# SZG-PMODshield-TXR.net
KiCad netlist of a schematic drawn in Altium Designer
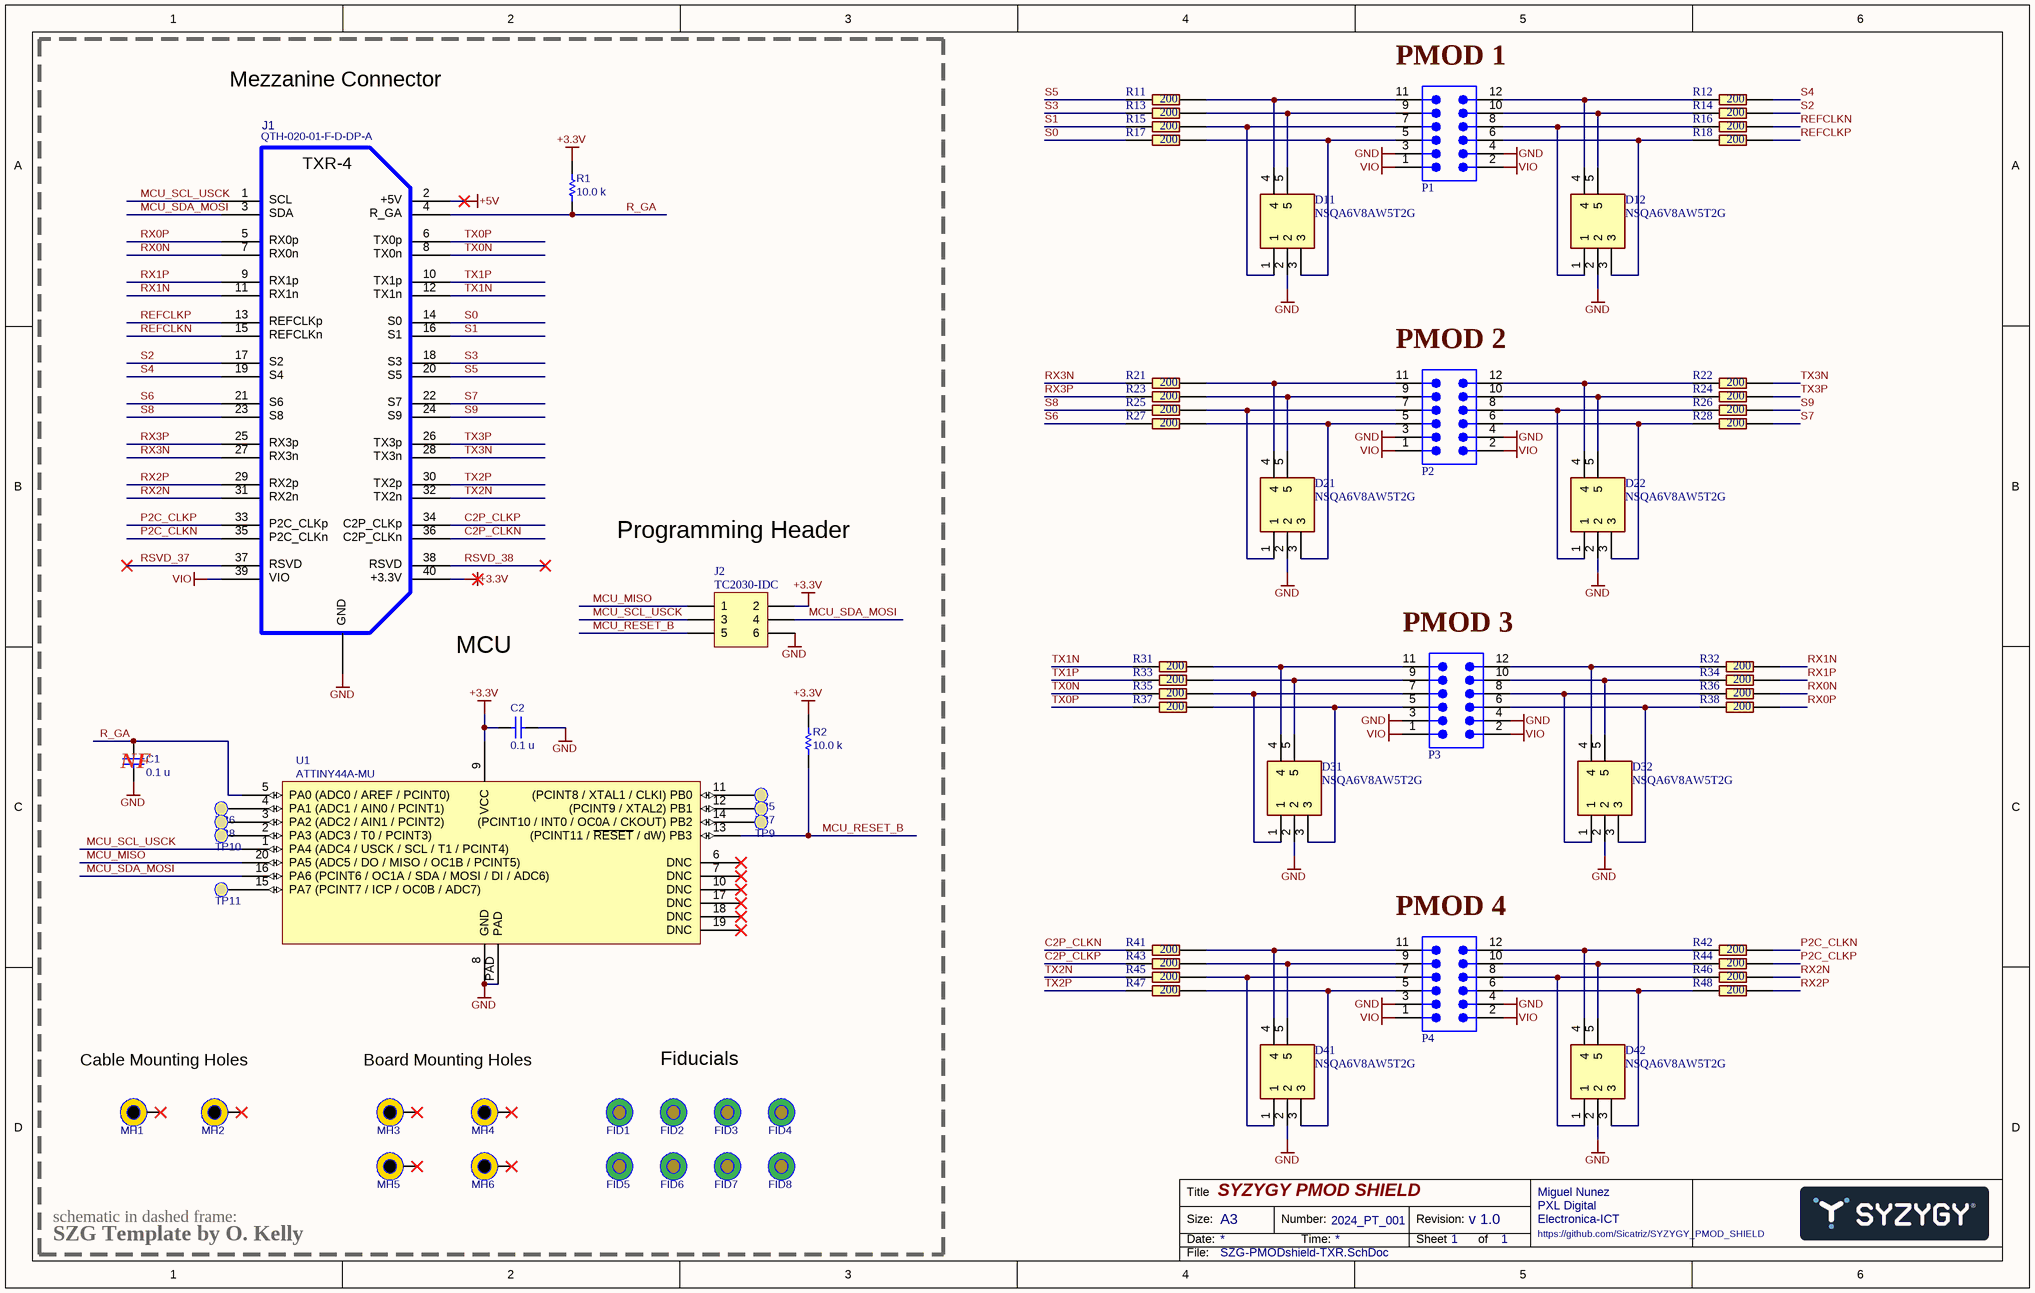
[diagram p0: SZG-PMODshield-TXR.SchDoc]

(export (version "E")
  (design (tool "Eeschema 10.0.6"))
  (components
    (comp (ref "C1")
      (value "0.1 u")
      (footprint "CAPC1005X06N")
      (description "Ceramic capacitor")
      (fields (field (name "MANUFACTURER") "Kemet") (field (name "PARTNUMBER") "000070"))
      (libsource (lib "Aligni") (part "Capacitor"))
    )
    (comp (ref "C2")
      (value "0.1 u")
      (footprint "CAPC1005X06N")
      (description "Ceramic capacitor")
      (fields (field (name "MANUFACTURER") "Kemet") (field (name "PARTNUMBER") "000070"))
      (libsource (lib "Aligni") (part "Capacitor"))
    )
    (comp (ref "D11")
      (value "NSQA6V8AW5T2G")
      (footprint "SZG-footprint-TXR:SOT65P210X110-5N")
      (description "Diode")
      (fields (field (name "MOUSER PART NUMBER") "863-NSQA6V8AW5T2G"))
      (libsource (lib "SZG-schematicLIB-TXR") (part "NSQA6V8AW5T2G"))
    )
    (comp (ref "D12")
      (value "NSQA6V8AW5T2G")
      (footprint "SZG-footprint-TXR:SOT65P210X110-5N")
      (description "Diode")
      (fields (field (name "MOUSER PART NUMBER") "863-NSQA6V8AW5T2G"))
      (libsource (lib "SZG-schematicLIB-TXR") (part "NSQA6V8AW5T2G"))
    )
    (comp (ref "D21")
      (value "NSQA6V8AW5T2G")
      (footprint "SZG-footprint-TXR:SOT65P210X110-5N")
      (description "Diode")
      (fields (field (name "MOUSER PART NUMBER") "863-NSQA6V8AW5T2G"))
      (libsource (lib "SZG-schematicLIB-TXR") (part "NSQA6V8AW5T2G"))
    )
    (comp (ref "D22")
      (value "NSQA6V8AW5T2G")
      (footprint "SZG-footprint-TXR:SOT65P210X110-5N")
      (description "Diode")
      (fields (field (name "MOUSER PART NUMBER") "863-NSQA6V8AW5T2G"))
      (libsource (lib "SZG-schematicLIB-TXR") (part "NSQA6V8AW5T2G"))
    )
    (comp (ref "D31")
      (value "NSQA6V8AW5T2G")
      (footprint "SZG-footprint-TXR:SOT65P210X110-5N")
      (description "Diode")
      (fields (field (name "MOUSER PART NUMBER") "863-NSQA6V8AW5T2G"))
      (libsource (lib "SZG-schematicLIB-TXR") (part "NSQA6V8AW5T2G"))
    )
    (comp (ref "D32")
      (value "NSQA6V8AW5T2G")
      (footprint "SZG-footprint-TXR:SOT65P210X110-5N")
      (description "Diode")
      (fields (field (name "MOUSER PART NUMBER") "863-NSQA6V8AW5T2G"))
      (libsource (lib "SZG-schematicLIB-TXR") (part "NSQA6V8AW5T2G"))
    )
    (comp (ref "D41")
      (value "NSQA6V8AW5T2G")
      (footprint "SZG-footprint-TXR:SOT65P210X110-5N")
      (description "Diode")
      (fields (field (name "MOUSER PART NUMBER") "863-NSQA6V8AW5T2G"))
      (libsource (lib "SZG-schematicLIB-TXR") (part "NSQA6V8AW5T2G"))
    )
    (comp (ref "D42")
      (value "NSQA6V8AW5T2G")
      (footprint "SZG-footprint-TXR:SOT65P210X110-5N")
      (description "Diode")
      (fields (field (name "MOUSER PART NUMBER") "863-NSQA6V8AW5T2G"))
      (libsource (lib "SZG-schematicLIB-TXR") (part "NSQA6V8AW5T2G"))
    )
    (comp (ref "FID1")
      (value "FIDUCIAL")
      (footprint "FID1MM/2MM-SS")
      (description "PCB fiducial")
      (libsource (lib "SZG-schematicLIB-TXR") (part "FIDUCIAL"))
    )
    (comp (ref "FID2")
      (value "FIDUCIAL")
      (footprint "FID1MM/2MM-SS")
      (description "PCB fiducial")
      (libsource (lib "SZG-schematicLIB-TXR") (part "FIDUCIAL"))
    )
    (comp (ref "FID3")
      (value "FIDUCIAL")
      (footprint "FID1MM/2MM-SS")
      (description "PCB fiducial")
      (libsource (lib "SZG-schematicLIB-TXR") (part "FIDUCIAL"))
    )
    (comp (ref "FID4")
      (value "FIDUCIAL")
      (footprint "FID1MM/2MM-SS")
      (description "PCB fiducial")
      (libsource (lib "SZG-schematicLIB-TXR") (part "FIDUCIAL"))
    )
    (comp (ref "FID5")
      (value "FIDUCIAL")
      (footprint "FID1MM/2MM-SS")
      (description "PCB fiducial")
      (libsource (lib "SZG-schematicLIB-TXR") (part "FIDUCIAL"))
    )
    (comp (ref "FID6")
      (value "FIDUCIAL")
      (footprint "FID1MM/2MM-SS")
      (description "PCB fiducial")
      (libsource (lib "SZG-schematicLIB-TXR") (part "FIDUCIAL"))
    )
    (comp (ref "FID7")
      (value "FIDUCIAL")
      (footprint "FID1MM/2MM-SS")
      (description "PCB fiducial")
      (libsource (lib "SZG-schematicLIB-TXR") (part "FIDUCIAL"))
    )
    (comp (ref "FID8")
      (value "FIDUCIAL")
      (footprint "FID1MM/2MM-SS")
      (description "PCB fiducial")
      (libsource (lib "SZG-schematicLIB-TXR") (part "FIDUCIAL"))
    )
    (comp (ref "J1")
      (value "40-pin, ground protection in middle")
      (footprint "QTH-020-01-X-D-DP-A-L")
      (description "0.5mm hi-speed, high-density header (female)")
      (fields
        (field (name "MANUFACTURER") "Samtec")
        (field (name "MANUFACTURER_PN") "QTH-020-01-F-D-DP-A")
        (field (name "ALIGNIPARTNUMBER") "001605")
      )
      (libsource (lib "Aligni") (part "QTH-DP_QSH-DP-020"))
    )
    (comp (ref "J2")
      (value "~")
      (footprint "TC2030-DUAL")
      (description "Tag-Connect 6-pin Plug-of-Nails spring-pin cable footprint")
      (fields
        (field (name "ALIGNIPARTNUMBER") "002062")
        (field (name "MANUFACTURER") "Tag-Connect")
        (field (name "MANUFACTURER_PN") "TC2030-IDC")
      )
      (libsource (lib "Aligni") (part "Header 3X2"))
    )
    (comp (ref "MH1")
      (value "MTG")
      (footprint "MTG-3.2/6.5-PTH")
      (description "Mounting hole")
      (libsource (lib "SZG-schematicLIB-TXR") (part "MTG"))
    )
    (comp (ref "MH2")
      (value "MTG")
      (footprint "MTG-3.2/6.5-PTH")
      (description "Mounting hole")
      (libsource (lib "SZG-schematicLIB-TXR") (part "MTG"))
    )
    (comp (ref "MH3")
      (value "MTG")
      (footprint "MTG-3.2/6.5-PTH")
      (description "Mounting hole")
      (libsource (lib "SZG-schematicLIB-TXR") (part "MTG"))
    )
    (comp (ref "MH4")
      (value "MTG")
      (footprint "MTG-3.2/6.5-PTH")
      (description "Mounting hole")
      (libsource (lib "SZG-schematicLIB-TXR") (part "MTG"))
    )
    (comp (ref "MH5")
      (value "MTG")
      (footprint "MTG-3.2/6.5-PTH")
      (description "Mounting hole")
      (libsource (lib "SZG-schematicLIB-TXR") (part "MTG"))
    )
    (comp (ref "MH6")
      (value "MTG")
      (footprint "MTG-3.2/6.5-PTH")
      (description "Mounting hole")
      (libsource (lib "SZG-schematicLIB-TXR") (part "MTG"))
    )
    (comp (ref "P1")
      (value "61301221021")
      (footprint "SZG-footprint-TXR:61301221021")
      (description "WR-PHD Pin Header, THT, Angled, pitch 2.54mm, 2 Row, 12P")
      (fields (field (name "MANUFACTURER") "Wurth Elektronik"))
      (libsource (lib "SZG-schematicLIB-TXR") (part "61301221021"))
    )
    (comp (ref "P2")
      (value "61301221021")
      (footprint "SZG-footprint-TXR:61301221021")
      (description "WR-PHD Pin Header, THT, Angled, pitch 2.54mm, 2 Row, 12P")
      (fields (field (name "MANUFACTURER") "Wurth Elektronik"))
      (libsource (lib "SZG-schematicLIB-TXR") (part "61301221021"))
    )
    (comp (ref "P3")
      (value "61301221121")
      (footprint "61301221121")
      (description "WR-PHD Pin Header, THT, Vertical, pitch 2.54mm, 2 Row, 12P")
      (fields (field (name "MANUFACTURER") "Wurth Elektronik"))
      (libsource (lib "SZG-schematicLIB-TXR") (part "61301221121"))
    )
    (comp (ref "P4")
      (value "61301221121")
      (footprint "61301221121")
      (description "WR-PHD Pin Header, THT, Vertical, pitch 2.54mm, 2 Row, 12P")
      (fields (field (name "MANUFACTURER") "Wurth Elektronik"))
      (libsource (lib "SZG-schematicLIB-TXR") (part "61301221121"))
    )
    (comp (ref "R1")
      (value "10.0 k")
      (footprint "RESC1005X06N")
      (description "Thick-film resistor")
      (fields (field (name "MANUFACTURER") "Vishay") (field (name "PARTNUMBER") "001521"))
      (libsource (lib "Aligni") (part "Resistor"))
    )
    (comp (ref "R2")
      (value "10.0 k")
      (footprint "RESC1005X06N")
      (description "Thick-film resistor")
      (fields (field (name "MANUFACTURER") "Vishay") (field (name "PARTNUMBER") "001521"))
      (libsource (lib "Aligni") (part "Resistor"))
    )
    (comp (ref "R11")
      (value "200")
      (footprint "SZG-footprint-TXR:RESC2012X50N")
      (description "Resistor")
      (fields (field (name "MANUFACTURER_PART_NUMBER") "CRCW08055K60JNEA"))
      (libsource (lib "SZG-schematicLIB-TXR") (part "0805_SMD_Resistor"))
    )
    (comp (ref "R12")
      (value "200")
      (footprint "SZG-footprint-TXR:RESC2012X50N")
      (description "Resistor")
      (fields (field (name "MANUFACTURER_PART_NUMBER") "CRCW08055K60JNEA"))
      (libsource (lib "SZG-schematicLIB-TXR") (part "0805_SMD_Resistor"))
    )
    (comp (ref "R13")
      (value "200")
      (footprint "SZG-footprint-TXR:RESC2012X50N")
      (description "Resistor")
      (fields (field (name "MANUFACTURER_PART_NUMBER") "CRCW08055K60JNEA"))
      (libsource (lib "SZG-schematicLIB-TXR") (part "0805_SMD_Resistor"))
    )
    (comp (ref "R14")
      (value "200")
      (footprint "SZG-footprint-TXR:RESC2012X50N")
      (description "Resistor")
      (fields (field (name "MANUFACTURER_PART_NUMBER") "CRCW08055K60JNEA"))
      (libsource (lib "SZG-schematicLIB-TXR") (part "0805_SMD_Resistor"))
    )
    (comp (ref "R15")
      (value "200")
      (footprint "SZG-footprint-TXR:RESC2012X50N")
      (description "Resistor")
      (fields (field (name "MANUFACTURER_PART_NUMBER") "CRCW08055K60JNEA"))
      (libsource (lib "SZG-schematicLIB-TXR") (part "0805_SMD_Resistor"))
    )
    (comp (ref "R16")
      (value "200")
      (footprint "SZG-footprint-TXR:RESC2012X50N")
      (description "Resistor")
      (fields (field (name "MANUFACTURER_PART_NUMBER") "CRCW08055K60JNEA"))
      (libsource (lib "SZG-schematicLIB-TXR") (part "0805_SMD_Resistor"))
    )
    (comp (ref "R17")
      (value "200")
      (footprint "SZG-footprint-TXR:RESC2012X50N")
      (description "Resistor")
      (fields (field (name "MANUFACTURER_PART_NUMBER") "CRCW08055K60JNEA"))
      (libsource (lib "SZG-schematicLIB-TXR") (part "0805_SMD_Resistor"))
    )
    (comp (ref "R18")
      (value "200")
      (footprint "SZG-footprint-TXR:RESC2012X50N")
      (description "Resistor")
      (fields (field (name "MANUFACTURER_PART_NUMBER") "CRCW08055K60JNEA"))
      (libsource (lib "SZG-schematicLIB-TXR") (part "0805_SMD_Resistor"))
    )
    (comp (ref "R21")
      (value "200")
      (footprint "SZG-footprint-TXR:RESC2012X50N")
      (description "Resistor")
      (fields (field (name "MANUFACTURER_PART_NUMBER") "CRCW08055K60JNEA"))
      (libsource (lib "SZG-schematicLIB-TXR") (part "0805_SMD_Resistor"))
    )
    (comp (ref "R22")
      (value "200")
      (footprint "SZG-footprint-TXR:RESC2012X50N")
      (description "Resistor")
      (fields (field (name "MANUFACTURER_PART_NUMBER") "CRCW08055K60JNEA"))
      (libsource (lib "SZG-schematicLIB-TXR") (part "0805_SMD_Resistor"))
    )
    (comp (ref "R23")
      (value "200")
      (footprint "SZG-footprint-TXR:RESC2012X50N")
      (description "Resistor")
      (fields (field (name "MANUFACTURER_PART_NUMBER") "CRCW08055K60JNEA"))
      (libsource (lib "SZG-schematicLIB-TXR") (part "0805_SMD_Resistor"))
    )
    (comp (ref "R24")
      (value "200")
      (footprint "SZG-footprint-TXR:RESC2012X50N")
      (description "Resistor")
      (fields (field (name "MANUFACTURER_PART_NUMBER") "CRCW08055K60JNEA"))
      (libsource (lib "SZG-schematicLIB-TXR") (part "0805_SMD_Resistor"))
    )
    (comp (ref "R25")
      (value "200")
      (footprint "SZG-footprint-TXR:RESC2012X50N")
      (description "Resistor")
      (fields (field (name "MANUFACTURER_PART_NUMBER") "CRCW08055K60JNEA"))
      (libsource (lib "SZG-schematicLIB-TXR") (part "0805_SMD_Resistor"))
    )
    (comp (ref "R26")
      (value "200")
      (footprint "SZG-footprint-TXR:RESC2012X50N")
      (description "Resistor")
      (fields (field (name "MANUFACTURER_PART_NUMBER") "CRCW08055K60JNEA"))
      (libsource (lib "SZG-schematicLIB-TXR") (part "0805_SMD_Resistor"))
    )
    (comp (ref "R27")
      (value "200")
      (footprint "SZG-footprint-TXR:RESC2012X50N")
      (description "Resistor")
      (fields (field (name "MANUFACTURER_PART_NUMBER") "CRCW08055K60JNEA"))
      (libsource (lib "SZG-schematicLIB-TXR") (part "0805_SMD_Resistor"))
    )
    (comp (ref "R28")
      (value "200")
      (footprint "SZG-footprint-TXR:RESC2012X50N")
      (description "Resistor")
      (fields (field (name "MANUFACTURER_PART_NUMBER") "CRCW08055K60JNEA"))
      (libsource (lib "SZG-schematicLIB-TXR") (part "0805_SMD_Resistor"))
    )
    (comp (ref "R31")
      (value "200")
      (footprint "SZG-footprint-TXR:RESC2012X50N")
      (description "Resistor")
      (fields (field (name "MANUFACTURER_PART_NUMBER") "CRCW08055K60JNEA"))
      (libsource (lib "SZG-schematicLIB-TXR") (part "0805_SMD_Resistor"))
    )
    (comp (ref "R32")
      (value "200")
      (footprint "SZG-footprint-TXR:RESC2012X50N")
      (description "Resistor")
      (fields (field (name "MANUFACTURER_PART_NUMBER") "CRCW08055K60JNEA"))
      (libsource (lib "SZG-schematicLIB-TXR") (part "0805_SMD_Resistor"))
    )
    (comp (ref "R33")
      (value "200")
      (footprint "SZG-footprint-TXR:RESC2012X50N")
      (description "Resistor")
      (fields (field (name "MANUFACTURER_PART_NUMBER") "CRCW08055K60JNEA"))
      (libsource (lib "SZG-schematicLIB-TXR") (part "0805_SMD_Resistor"))
    )
    (comp (ref "R34")
      (value "200")
      (footprint "SZG-footprint-TXR:RESC2012X50N")
      (description "Resistor")
      (fields (field (name "MANUFACTURER_PART_NUMBER") "CRCW08055K60JNEA"))
      (libsource (lib "SZG-schematicLIB-TXR") (part "0805_SMD_Resistor"))
    )
    (comp (ref "R35")
      (value "200")
      (footprint "SZG-footprint-TXR:RESC2012X50N")
      (description "Resistor")
      (fields (field (name "MANUFACTURER_PART_NUMBER") "CRCW08055K60JNEA"))
      (libsource (lib "SZG-schematicLIB-TXR") (part "0805_SMD_Resistor"))
    )
    (comp (ref "R36")
      (value "200")
      (footprint "SZG-footprint-TXR:RESC2012X50N")
      (description "Resistor")
      (fields (field (name "MANUFACTURER_PART_NUMBER") "CRCW08055K60JNEA"))
      (libsource (lib "SZG-schematicLIB-TXR") (part "0805_SMD_Resistor"))
    )
    (comp (ref "R37")
      (value "200")
      (footprint "SZG-footprint-TXR:RESC2012X50N")
      (description "Resistor")
      (fields (field (name "MANUFACTURER_PART_NUMBER") "CRCW08055K60JNEA"))
      (libsource (lib "SZG-schematicLIB-TXR") (part "0805_SMD_Resistor"))
    )
    (comp (ref "R38")
      (value "200")
      (footprint "SZG-footprint-TXR:RESC2012X50N")
      (description "Resistor")
      (fields (field (name "MANUFACTURER_PART_NUMBER") "CRCW08055K60JNEA"))
      (libsource (lib "SZG-schematicLIB-TXR") (part "0805_SMD_Resistor"))
    )
    (comp (ref "R41")
      (value "200")
      (footprint "SZG-footprint-TXR:RESC2012X50N")
      (description "Resistor")
      (fields (field (name "MANUFACTURER_PART_NUMBER") "CRCW08055K60JNEA"))
      (libsource (lib "SZG-schematicLIB-TXR") (part "0805_SMD_Resistor"))
    )
    (comp (ref "R42")
      (value "200")
      (footprint "SZG-footprint-TXR:RESC2012X50N")
      (description "Resistor")
      (fields (field (name "MANUFACTURER_PART_NUMBER") "CRCW08055K60JNEA"))
      (libsource (lib "SZG-schematicLIB-TXR") (part "0805_SMD_Resistor"))
    )
    (comp (ref "R43")
      (value "200")
      (footprint "SZG-footprint-TXR:RESC2012X50N")
      (description "Resistor")
      (fields (field (name "MANUFACTURER_PART_NUMBER") "CRCW08055K60JNEA"))
      (libsource (lib "SZG-schematicLIB-TXR") (part "0805_SMD_Resistor"))
    )
    (comp (ref "R44")
      (value "200")
      (footprint "SZG-footprint-TXR:RESC2012X50N")
      (description "Resistor")
      (fields (field (name "MANUFACTURER_PART_NUMBER") "CRCW08055K60JNEA"))
      (libsource (lib "SZG-schematicLIB-TXR") (part "0805_SMD_Resistor"))
    )
    (comp (ref "R45")
      (value "200")
      (footprint "SZG-footprint-TXR:RESC2012X50N")
      (description "Resistor")
      (fields (field (name "MANUFACTURER_PART_NUMBER") "CRCW08055K60JNEA"))
      (libsource (lib "SZG-schematicLIB-TXR") (part "0805_SMD_Resistor"))
    )
    (comp (ref "R46")
      (value "200")
      (footprint "SZG-footprint-TXR:RESC2012X50N")
      (description "Resistor")
      (fields (field (name "MANUFACTURER_PART_NUMBER") "CRCW08055K60JNEA"))
      (libsource (lib "SZG-schematicLIB-TXR") (part "0805_SMD_Resistor"))
    )
    (comp (ref "R47")
      (value "200")
      (footprint "SZG-footprint-TXR:RESC2012X50N")
      (description "Resistor")
      (fields (field (name "MANUFACTURER_PART_NUMBER") "CRCW08055K60JNEA"))
      (libsource (lib "SZG-schematicLIB-TXR") (part "0805_SMD_Resistor"))
    )
    (comp (ref "R48")
      (value "200")
      (footprint "SZG-footprint-TXR:RESC2012X50N")
      (description "Resistor")
      (fields (field (name "MANUFACTURER_PART_NUMBER") "CRCW08055K60JNEA"))
      (libsource (lib "SZG-schematicLIB-TXR") (part "0805_SMD_Resistor"))
    )
    (comp (ref "TP5")
      (value "TESTPOINT-SMD20")
      (footprint "TP-SMD20")
      (description "Test point, surface-mount, 20mil")
      (libsource (lib "SZG-schematicLIB-TXR") (part "TESTPOINT-SMD20"))
    )
    (comp (ref "TP6")
      (value "TESTPOINT-SMD20")
      (footprint "TP-SMD20")
      (description "Test point, surface-mount, 20mil")
      (libsource (lib "SZG-schematicLIB-TXR") (part "TESTPOINT-SMD20"))
    )
    (comp (ref "TP7")
      (value "TESTPOINT-SMD20")
      (footprint "TP-SMD20")
      (description "Test point, surface-mount, 20mil")
      (libsource (lib "SZG-schematicLIB-TXR") (part "TESTPOINT-SMD20"))
    )
    (comp (ref "TP8")
      (value "TESTPOINT-SMD20")
      (footprint "TP-SMD20")
      (description "Test point, surface-mount, 20mil")
      (libsource (lib "SZG-schematicLIB-TXR") (part "TESTPOINT-SMD20"))
    )
    (comp (ref "TP9")
      (value "TESTPOINT-SMD20")
      (footprint "TP-SMD20")
      (description "Test point, surface-mount, 20mil")
      (libsource (lib "SZG-schematicLIB-TXR") (part "TESTPOINT-SMD20"))
    )
    (comp (ref "TP10")
      (value "TESTPOINT-SMD20")
      (footprint "TP-SMD20")
      (description "Test point, surface-mount, 20mil")
      (libsource (lib "SZG-schematicLIB-TXR") (part "TESTPOINT-SMD20"))
    )
    (comp (ref "TP11")
      (value "TESTPOINT-SMD20")
      (footprint "TP-SMD20")
      (description "Test point, surface-mount, 20mil")
      (libsource (lib "SZG-schematicLIB-TXR") (part "TESTPOINT-SMD20"))
    )
    (comp (ref "U1")
      (value "ATTINY44A-MU")
      (footprint "QFN-EP-20")
      (description "8-bit MCU, 4 KB flash, 256 bytes EEPROM")
      (fields (field (name "MANUFACTURER") "Microchip") (field (name "PARTNUMBER") "001552"))
      (libsource (lib "Aligni") (part "ATTINYx4A-MU"))
    )
  )
  (nets
    (net (code "1") (name "+3.3V") (class "Default")
      (node (ref "C2") (pin "2") (pinfunction "2_2") (pintype "passive"))
      (node (ref "J1") (pin "40") (pinfunction "40_40") (pintype "passive"))
      (node (ref "J2") (pin "2") (pinfunction "2_2") (pintype "passive"))
      (node (ref "R1") (pin "2") (pinfunction "2_2") (pintype "passive"))
      (node (ref "R2") (pin "2") (pinfunction "2_2") (pintype "passive"))
      (node (ref "U1") (pin "9") (pinfunction "VCC_9") (pintype "power_in"))
    )
    (net (code "2") (name "+5V") (class "Default")
      (node (ref "J1") (pin "2") (pinfunction "2_2") (pintype "passive"))
    )
    (net (code "3") (name "/C2P_CLKN") (class "Default")
      (node (ref "J1") (pin "36") (pinfunction "36_36") (pintype "passive"))
      (node (ref "R41") (pin "1") (pinfunction "1_1") (pintype "passive"))
    )
    (net (code "4") (name "/C2P_CLKP") (class "Default")
      (node (ref "J1") (pin "34") (pinfunction "34_34") (pintype "passive"))
      (node (ref "R43") (pin "1") (pinfunction "1_1") (pintype "passive"))
    )
    (net (code "5") (name "/MCU_MISO") (class "Default")
      (node (ref "J2") (pin "1") (pinfunction "1_1") (pintype "passive"))
      (node (ref "U1") (pin "20") (pinfunction "PA5_(ADC5_/_DO_/_MISO_/_OC1B_/_PCINT5)_20") (pintype "bidirectional"))
    )
    (net (code "6") (name "/MCU_RESET_B") (class "Default")
      (node (ref "J2") (pin "5") (pinfunction "5_5") (pintype "passive"))
      (node (ref "R2") (pin "1") (pinfunction "1_1") (pintype "passive"))
      (node (ref "U1") (pin "13") (pinfunction "(PCINT11_/_~{RESET}_/_dW)_PB3_13") (pintype "bidirectional"))
    )
    (net (code "7") (name "/MCU_SCL_USCK") (class "Default")
      (node (ref "J1") (pin "1") (pinfunction "1_1") (pintype "passive"))
      (node (ref "J2") (pin "3") (pinfunction "3_3") (pintype "passive"))
      (node (ref "U1") (pin "1") (pinfunction "PA4_(ADC4_/_USCK_/_SCL_/_T1_/_PCINT4)_1") (pintype "bidirectional"))
    )
    (net (code "8") (name "/MCU_SDA_MOSI") (class "Default")
      (node (ref "J1") (pin "3") (pinfunction "3_3") (pintype "passive"))
      (node (ref "J2") (pin "4") (pinfunction "4_4") (pintype "passive"))
      (node (ref "U1") (pin "16") (pinfunction "PA6_(PCINT6_/_OC1A_/_SDA_/_MOSI_/_DI_/_ADC6)_16") (pintype "bidirectional"))
    )
    (net (code "9") (name "/P2C_CLKN") (class "Default")
      (node (ref "J1") (pin "35") (pinfunction "35_35") (pintype "passive"))
      (node (ref "R42") (pin "2") (pinfunction "2_2") (pintype "passive"))
    )
    (net (code "10") (name "/P2C_CLKP") (class "Default")
      (node (ref "J1") (pin "33") (pinfunction "33_33") (pintype "passive"))
      (node (ref "R44") (pin "2") (pinfunction "2_2") (pintype "passive"))
    )
    (net (code "11") (name "/REFCLKN") (class "Default")
      (node (ref "J1") (pin "15") (pinfunction "15_15") (pintype "passive"))
      (node (ref "R16") (pin "2") (pinfunction "2_2") (pintype "passive"))
    )
    (net (code "12") (name "/REFCLKP") (class "Default")
      (node (ref "J1") (pin "13") (pinfunction "13_13") (pintype "passive"))
      (node (ref "R18") (pin "2") (pinfunction "2_2") (pintype "passive"))
    )
    (net (code "13") (name "/RSVD_37") (class "Default")
      (node (ref "J1") (pin "37") (pinfunction "37_37") (pintype "passive+no_connect"))
    )
    (net (code "14") (name "/RSVD_38") (class "Default")
      (node (ref "J1") (pin "38") (pinfunction "38_38") (pintype "passive+no_connect"))
    )
    (net (code "15") (name "/RX0N") (class "Default")
      (node (ref "J1") (pin "7") (pinfunction "7_7") (pintype "passive"))
      (node (ref "R36") (pin "2") (pinfunction "2_2") (pintype "passive"))
    )
    (net (code "16") (name "/RX0P") (class "Default")
      (node (ref "J1") (pin "5") (pinfunction "5_5") (pintype "passive"))
      (node (ref "R38") (pin "2") (pinfunction "2_2") (pintype "passive"))
    )
    (net (code "17") (name "/RX1N") (class "Default")
      (node (ref "J1") (pin "11") (pinfunction "11_11") (pintype "passive"))
      (node (ref "R32") (pin "2") (pinfunction "2_2") (pintype "passive"))
    )
    (net (code "18") (name "/RX1P") (class "Default")
      (node (ref "J1") (pin "9") (pinfunction "9_9") (pintype "passive"))
      (node (ref "R34") (pin "2") (pinfunction "2_2") (pintype "passive"))
    )
    (net (code "19") (name "/RX2N") (class "Default")
      (node (ref "J1") (pin "31") (pinfunction "31_31") (pintype "passive"))
      (node (ref "R46") (pin "2") (pinfunction "2_2") (pintype "passive"))
    )
    (net (code "20") (name "/RX2P") (class "Default")
      (node (ref "J1") (pin "29") (pinfunction "29_29") (pintype "passive"))
      (node (ref "R48") (pin "2") (pinfunction "2_2") (pintype "passive"))
    )
    (net (code "21") (name "/RX3N") (class "Default")
      (node (ref "J1") (pin "27") (pinfunction "27_27") (pintype "passive"))
      (node (ref "R21") (pin "1") (pinfunction "1_1") (pintype "passive"))
    )
    (net (code "22") (name "/RX3P") (class "Default")
      (node (ref "J1") (pin "25") (pinfunction "25_25") (pintype "passive"))
      (node (ref "R23") (pin "1") (pinfunction "1_1") (pintype "passive"))
    )
    (net (code "23") (name "/R_GA") (class "Default")
      (node (ref "C1") (pin "2") (pinfunction "2_2") (pintype "passive"))
      (node (ref "J1") (pin "4") (pinfunction "4_4") (pintype "passive"))
      (node (ref "R1") (pin "1") (pinfunction "1_1") (pintype "passive"))
      (node (ref "U1") (pin "5") (pinfunction "PA0_(ADC0_/_AREF_/_PCINT0)_5") (pintype "bidirectional"))
    )
    (net (code "24") (name "/S0") (class "Default")
      (node (ref "J1") (pin "14") (pinfunction "14_14") (pintype "passive"))
      (node (ref "R17") (pin "1") (pinfunction "1_1") (pintype "passive"))
    )
    (net (code "25") (name "/S1") (class "Default")
      (node (ref "J1") (pin "16") (pinfunction "16_16") (pintype "passive"))
      (node (ref "R15") (pin "1") (pinfunction "1_1") (pintype "passive"))
    )
    (net (code "26") (name "/S2") (class "Default")
      (node (ref "J1") (pin "17") (pinfunction "17_17") (pintype "passive"))
      (node (ref "R14") (pin "2") (pinfunction "2_2") (pintype "passive"))
    )
    (net (code "27") (name "/S3") (class "Default")
      (node (ref "J1") (pin "18") (pinfunction "18_18") (pintype "passive"))
      (node (ref "R13") (pin "1") (pinfunction "1_1") (pintype "passive"))
    )
    (net (code "28") (name "/S4") (class "Default")
      (node (ref "J1") (pin "19") (pinfunction "19_19") (pintype "passive"))
      (node (ref "R12") (pin "2") (pinfunction "2_2") (pintype "passive"))
    )
    (net (code "29") (name "/S5") (class "Default")
      (node (ref "J1") (pin "20") (pinfunction "20_20") (pintype "passive"))
      (node (ref "R11") (pin "1") (pinfunction "1_1") (pintype "passive"))
    )
    (net (code "30") (name "/S6") (class "Default")
      (node (ref "J1") (pin "21") (pinfunction "21_21") (pintype "passive"))
      (node (ref "R27") (pin "1") (pinfunction "1_1") (pintype "passive"))
    )
    (net (code "31") (name "/S7") (class "Default")
      (node (ref "J1") (pin "22") (pinfunction "22_22") (pintype "passive"))
      (node (ref "R28") (pin "2") (pinfunction "2_2") (pintype "passive"))
    )
    (net (code "32") (name "/S8") (class "Default")
      (node (ref "J1") (pin "23") (pinfunction "23_23") (pintype "passive"))
      (node (ref "R25") (pin "1") (pinfunction "1_1") (pintype "passive"))
    )
    (net (code "33") (name "/S9") (class "Default")
      (node (ref "J1") (pin "24") (pinfunction "24_24") (pintype "passive"))
      (node (ref "R26") (pin "2") (pinfunction "2_2") (pintype "passive"))
    )
    (net (code "34") (name "/TX0N") (class "Default")
      (node (ref "J1") (pin "8") (pinfunction "8_8") (pintype "passive"))
      (node (ref "R35") (pin "1") (pinfunction "1_1") (pintype "passive"))
    )
    (net (code "35") (name "/TX0P") (class "Default")
      (node (ref "J1") (pin "6") (pinfunction "6_6") (pintype "passive"))
      (node (ref "R37") (pin "1") (pinfunction "1_1") (pintype "passive"))
    )
    (net (code "36") (name "/TX1N") (class "Default")
      (node (ref "J1") (pin "12") (pinfunction "12_12") (pintype "passive"))
      (node (ref "R31") (pin "1") (pinfunction "1_1") (pintype "passive"))
    )
    (net (code "37") (name "/TX1P") (class "Default")
      (node (ref "J1") (pin "10") (pinfunction "10_10") (pintype "passive"))
      (node (ref "R33") (pin "1") (pinfunction "1_1") (pintype "passive"))
    )
    (net (code "38") (name "/TX2N") (class "Default")
      (node (ref "J1") (pin "32") (pinfunction "32_32") (pintype "passive"))
      (node (ref "R45") (pin "1") (pinfunction "1_1") (pintype "passive"))
    )
    (net (code "39") (name "/TX2P") (class "Default")
      (node (ref "J1") (pin "30") (pinfunction "30_30") (pintype "passive"))
      (node (ref "R47") (pin "1") (pinfunction "1_1") (pintype "passive"))
    )
    (net (code "40") (name "/TX3N") (class "Default")
      (node (ref "J1") (pin "28") (pinfunction "28_28") (pintype "passive"))
      (node (ref "R22") (pin "2") (pinfunction "2_2") (pintype "passive"))
    )
    (net (code "41") (name "/TX3P") (class "Default")
      (node (ref "J1") (pin "26") (pinfunction "26_26") (pintype "passive"))
      (node (ref "R24") (pin "2") (pinfunction "2_2") (pintype "passive"))
    )
    (net (code "42") (name "GND") (class "Default")
      (node (ref "C1") (pin "1") (pinfunction "1_1") (pintype "passive"))
      (node (ref "C2") (pin "1") (pinfunction "1_1") (pintype "passive"))
      (node (ref "D11") (pin "2") (pinfunction "2_2") (pintype "passive"))
      (node (ref "D12") (pin "2") (pinfunction "2_2") (pintype "passive"))
      (node (ref "D21") (pin "2") (pinfunction "2_2") (pintype "passive"))
      (node (ref "D22") (pin "2") (pinfunction "2_2") (pintype "passive"))
      (node (ref "D31") (pin "2") (pinfunction "2_2") (pintype "passive"))
      (node (ref "D32") (pin "2") (pinfunction "2_2") (pintype "passive"))
      (node (ref "D41") (pin "2") (pinfunction "2_2") (pintype "passive"))
      (node (ref "D42") (pin "2") (pinfunction "2_2") (pintype "passive"))
      (node (ref "J1") (pin "0") (pinfunction "GND_0") (pintype "passive"))
      (node (ref "J2") (pin "6") (pinfunction "6_6") (pintype "passive"))
      (node (ref "P1") (pin "3") (pinfunction "3_3") (pintype "passive"))
      (node (ref "P1") (pin "4") (pinfunction "4_4") (pintype "passive"))
      (node (ref "P2") (pin "3") (pinfunction "3_3") (pintype "passive"))
      (node (ref "P2") (pin "4") (pinfunction "4_4") (pintype "passive"))
      (node (ref "P3") (pin "3") (pinfunction "3_3") (pintype "passive"))
      (node (ref "P3") (pin "4") (pinfunction "4_4") (pintype "passive"))
      (node (ref "P4") (pin "3") (pinfunction "3_3") (pintype "passive"))
      (node (ref "P4") (pin "4") (pinfunction "4_4") (pintype "passive"))
      (node (ref "U1") (pin "8") (pinfunction "GND_8") (pintype "power_in"))
      (node (ref "U1") (pin "PAD") (pinfunction "PAD_PAD") (pintype "power_in"))
    )
    (net (code "43") (name "Net-(D11-Pad1)") (class "Default")
      (node (ref "D11") (pin "1") (pinfunction "1_1") (pintype "passive"))
      (node (ref "P1") (pin "7") (pinfunction "7_7") (pintype "passive"))
      (node (ref "R15") (pin "2") (pinfunction "2_2") (pintype "passive"))
    )
    (net (code "44") (name "Net-(D11-Pad3)") (class "Default")
      (node (ref "D11") (pin "3") (pinfunction "3_3") (pintype "passive"))
      (node (ref "P1") (pin "5") (pinfunction "5_5") (pintype "passive"))
      (node (ref "R17") (pin "2") (pinfunction "2_2") (pintype "passive"))
    )
    (net (code "45") (name "Net-(D11-Pad4)") (class "Default")
      (node (ref "D11") (pin "4") (pinfunction "4_4") (pintype "passive"))
      (node (ref "P1") (pin "11") (pinfunction "11_11") (pintype "passive"))
      (node (ref "R11") (pin "2") (pinfunction "2_2") (pintype "passive"))
    )
    (net (code "46") (name "Net-(D11-Pad5)") (class "Default")
      (node (ref "D11") (pin "5") (pinfunction "5_5") (pintype "passive"))
      (node (ref "P1") (pin "9") (pinfunction "9_9") (pintype "passive"))
      (node (ref "R13") (pin "2") (pinfunction "2_2") (pintype "passive"))
    )
    (net (code "47") (name "Net-(D12-Pad1)") (class "Default")
      (node (ref "D12") (pin "1") (pinfunction "1_1") (pintype "passive"))
      (node (ref "P1") (pin "8") (pinfunction "8_8") (pintype "passive"))
      (node (ref "R16") (pin "1") (pinfunction "1_1") (pintype "passive"))
    )
    (net (code "48") (name "Net-(D12-Pad3)") (class "Default")
      (node (ref "D12") (pin "3") (pinfunction "3_3") (pintype "passive"))
      (node (ref "P1") (pin "6") (pinfunction "6_6") (pintype "passive"))
      (node (ref "R18") (pin "1") (pinfunction "1_1") (pintype "passive"))
    )
    (net (code "49") (name "Net-(D12-Pad4)") (class "Default")
      (node (ref "D12") (pin "4") (pinfunction "4_4") (pintype "passive"))
      (node (ref "P1") (pin "12") (pinfunction "12_12") (pintype "passive"))
      (node (ref "R12") (pin "1") (pinfunction "1_1") (pintype "passive"))
    )
    (net (code "50") (name "Net-(D12-Pad5)") (class "Default")
      (node (ref "D12") (pin "5") (pinfunction "5_5") (pintype "passive"))
      (node (ref "P1") (pin "10") (pinfunction "10_10") (pintype "passive"))
      (node (ref "R14") (pin "1") (pinfunction "1_1") (pintype "passive"))
    )
    (net (code "51") (name "Net-(D21-Pad1)") (class "Default")
      (node (ref "D21") (pin "1") (pinfunction "1_1") (pintype "passive"))
      (node (ref "P2") (pin "7") (pinfunction "7_7") (pintype "passive"))
      (node (ref "R25") (pin "2") (pinfunction "2_2") (pintype "passive"))
    )
    (net (code "52") (name "Net-(D21-Pad3)") (class "Default")
      (node (ref "D21") (pin "3") (pinfunction "3_3") (pintype "passive"))
      (node (ref "P2") (pin "5") (pinfunction "5_5") (pintype "passive"))
      (node (ref "R27") (pin "2") (pinfunction "2_2") (pintype "passive"))
    )
    (net (code "53") (name "Net-(D21-Pad4)") (class "Default")
      (node (ref "D21") (pin "4") (pinfunction "4_4") (pintype "passive"))
      (node (ref "P2") (pin "11") (pinfunction "11_11") (pintype "passive"))
      (node (ref "R21") (pin "2") (pinfunction "2_2") (pintype "passive"))
    )
    (net (code "54") (name "Net-(D21-Pad5)") (class "Default")
      (node (ref "D21") (pin "5") (pinfunction "5_5") (pintype "passive"))
      (node (ref "P2") (pin "9") (pinfunction "9_9") (pintype "passive"))
      (node (ref "R23") (pin "2") (pinfunction "2_2") (pintype "passive"))
    )
    (net (code "55") (name "Net-(D22-Pad1)") (class "Default")
      (node (ref "D22") (pin "1") (pinfunction "1_1") (pintype "passive"))
      (node (ref "P2") (pin "8") (pinfunction "8_8") (pintype "passive"))
      (node (ref "R26") (pin "1") (pinfunction "1_1") (pintype "passive"))
    )
    (net (code "56") (name "Net-(D22-Pad3)") (class "Default")
      (node (ref "D22") (pin "3") (pinfunction "3_3") (pintype "passive"))
      (node (ref "P2") (pin "6") (pinfunction "6_6") (pintype "passive"))
      (node (ref "R28") (pin "1") (pinfunction "1_1") (pintype "passive"))
    )
    (net (code "57") (name "Net-(D22-Pad4)") (class "Default")
      (node (ref "D22") (pin "4") (pinfunction "4_4") (pintype "passive"))
      (node (ref "P2") (pin "12") (pinfunction "12_12") (pintype "passive"))
      (node (ref "R22") (pin "1") (pinfunction "1_1") (pintype "passive"))
    )
    (net (code "58") (name "Net-(D22-Pad5)") (class "Default")
      (node (ref "D22") (pin "5") (pinfunction "5_5") (pintype "passive"))
      (node (ref "P2") (pin "10") (pinfunction "10_10") (pintype "passive"))
      (node (ref "R24") (pin "1") (pinfunction "1_1") (pintype "passive"))
    )
    (net (code "59") (name "Net-(D31-Pad1)") (class "Default")
      (node (ref "D31") (pin "1") (pinfunction "1_1") (pintype "passive"))
      (node (ref "P3") (pin "7") (pinfunction "7_7") (pintype "passive"))
      (node (ref "R35") (pin "2") (pinfunction "2_2") (pintype "passive"))
    )
    (net (code "60") (name "Net-(D31-Pad3)") (class "Default")
      (node (ref "D31") (pin "3") (pinfunction "3_3") (pintype "passive"))
      (node (ref "P3") (pin "5") (pinfunction "5_5") (pintype "passive"))
      (node (ref "R37") (pin "2") (pinfunction "2_2") (pintype "passive"))
    )
    (net (code "61") (name "Net-(D31-Pad4)") (class "Default")
      (node (ref "D31") (pin "4") (pinfunction "4_4") (pintype "passive"))
      (node (ref "P3") (pin "11") (pinfunction "11_11") (pintype "passive"))
      (node (ref "R31") (pin "2") (pinfunction "2_2") (pintype "passive"))
    )
    (net (code "62") (name "Net-(D31-Pad5)") (class "Default")
      (node (ref "D31") (pin "5") (pinfunction "5_5") (pintype "passive"))
      (node (ref "P3") (pin "9") (pinfunction "9_9") (pintype "passive"))
      (node (ref "R33") (pin "2") (pinfunction "2_2") (pintype "passive"))
    )
    (net (code "63") (name "Net-(D32-Pad1)") (class "Default")
      (node (ref "D32") (pin "1") (pinfunction "1_1") (pintype "passive"))
      (node (ref "P3") (pin "8") (pinfunction "8_8") (pintype "passive"))
      (node (ref "R36") (pin "1") (pinfunction "1_1") (pintype "passive"))
    )
    (net (code "64") (name "Net-(D32-Pad3)") (class "Default")
      (node (ref "D32") (pin "3") (pinfunction "3_3") (pintype "passive"))
      (node (ref "P3") (pin "6") (pinfunction "6_6") (pintype "passive"))
      (node (ref "R38") (pin "1") (pinfunction "1_1") (pintype "passive"))
    )
    (net (code "65") (name "Net-(D32-Pad4)") (class "Default")
      (node (ref "D32") (pin "4") (pinfunction "4_4") (pintype "passive"))
      (node (ref "P3") (pin "12") (pinfunction "12_12") (pintype "passive"))
      (node (ref "R32") (pin "1") (pinfunction "1_1") (pintype "passive"))
    )
    (net (code "66") (name "Net-(D32-Pad5)") (class "Default")
      (node (ref "D32") (pin "5") (pinfunction "5_5") (pintype "passive"))
      (node (ref "P3") (pin "10") (pinfunction "10_10") (pintype "passive"))
      (node (ref "R34") (pin "1") (pinfunction "1_1") (pintype "passive"))
    )
    (net (code "67") (name "Net-(D41-Pad1)") (class "Default")
      (node (ref "D41") (pin "1") (pinfunction "1_1") (pintype "passive"))
      (node (ref "P4") (pin "7") (pinfunction "7_7") (pintype "passive"))
      (node (ref "R45") (pin "2") (pinfunction "2_2") (pintype "passive"))
    )
    (net (code "68") (name "Net-(D41-Pad3)") (class "Default")
      (node (ref "D41") (pin "3") (pinfunction "3_3") (pintype "passive"))
      (node (ref "P4") (pin "5") (pinfunction "5_5") (pintype "passive"))
      (node (ref "R47") (pin "2") (pinfunction "2_2") (pintype "passive"))
    )
    (net (code "69") (name "Net-(D41-Pad4)") (class "Default")
      (node (ref "D41") (pin "4") (pinfunction "4_4") (pintype "passive"))
      (node (ref "P4") (pin "11") (pinfunction "11_11") (pintype "passive"))
      (node (ref "R41") (pin "2") (pinfunction "2_2") (pintype "passive"))
    )
    (net (code "70") (name "Net-(D41-Pad5)") (class "Default")
      (node (ref "D41") (pin "5") (pinfunction "5_5") (pintype "passive"))
      (node (ref "P4") (pin "9") (pinfunction "9_9") (pintype "passive"))
      (node (ref "R43") (pin "2") (pinfunction "2_2") (pintype "passive"))
    )
    (net (code "71") (name "Net-(D42-Pad1)") (class "Default")
      (node (ref "D42") (pin "1") (pinfunction "1_1") (pintype "passive"))
      (node (ref "P4") (pin "8") (pinfunction "8_8") (pintype "passive"))
      (node (ref "R46") (pin "1") (pinfunction "1_1") (pintype "passive"))
    )
    (net (code "72") (name "Net-(D42-Pad3)") (class "Default")
      (node (ref "D42") (pin "3") (pinfunction "3_3") (pintype "passive"))
      (node (ref "P4") (pin "6") (pinfunction "6_6") (pintype "passive"))
      (node (ref "R48") (pin "1") (pinfunction "1_1") (pintype "passive"))
    )
    (net (code "73") (name "Net-(D42-Pad4)") (class "Default")
      (node (ref "D42") (pin "4") (pinfunction "4_4") (pintype "passive"))
      (node (ref "P4") (pin "12") (pinfunction "12_12") (pintype "passive"))
      (node (ref "R42") (pin "1") (pinfunction "1_1") (pintype "passive"))
    )
    (net (code "74") (name "Net-(D42-Pad5)") (class "Default")
      (node (ref "D42") (pin "5") (pinfunction "5_5") (pintype "passive"))
      (node (ref "P4") (pin "10") (pinfunction "10_10") (pintype "passive"))
      (node (ref "R44") (pin "1") (pinfunction "1_1") (pintype "passive"))
    )
    (net (code "75") (name "Net-(TP5-PIN)") (class "Default")
      (node (ref "TP5") (pin "1") (pinfunction "PIN_1") (pintype "passive"))
      (node (ref "U1") (pin "11") (pinfunction "(PCINT8_/_XTAL1_/_CLKI)_PB0_11") (pintype "bidirectional"))
    )
    (net (code "76") (name "Net-(TP6-PIN)") (class "Default")
      (node (ref "TP6") (pin "1") (pinfunction "PIN_1") (pintype "passive"))
      (node (ref "U1") (pin "4") (pinfunction "PA1_(ADC1_/_AIN0_/_PCINT1)_4") (pintype "bidirectional"))
    )
    (net (code "77") (name "Net-(TP7-PIN)") (class "Default")
      (node (ref "TP7") (pin "1") (pinfunction "PIN_1") (pintype "passive"))
      (node (ref "U1") (pin "12") (pinfunction "(PCINT9_/_XTAL2)_PB1_12") (pintype "bidirectional"))
    )
    (net (code "78") (name "Net-(TP8-PIN)") (class "Default")
      (node (ref "TP8") (pin "1") (pinfunction "PIN_1") (pintype "passive"))
      (node (ref "U1") (pin "3") (pinfunction "PA2_(ADC2_/_AIN1_/_PCINT2)_3") (pintype "bidirectional"))
    )
    (net (code "79") (name "Net-(TP9-PIN)") (class "Default")
      (node (ref "TP9") (pin "1") (pinfunction "PIN_1") (pintype "passive"))
      (node (ref "U1") (pin "14") (pinfunction "(PCINT10_/_INT0_/_OC0A_/_CKOUT)_PB2_14") (pintype "bidirectional"))
    )
    (net (code "80") (name "Net-(TP10-PIN)") (class "Default")
      (node (ref "TP10") (pin "1") (pinfunction "PIN_1") (pintype "passive"))
      (node (ref "U1") (pin "2") (pinfunction "PA3_(ADC3_/_T0_/_PCINT3)_2") (pintype "bidirectional"))
    )
    (net (code "81") (name "Net-(TP11-PIN)") (class "Default")
      (node (ref "TP11") (pin "1") (pinfunction "PIN_1") (pintype "passive"))
      (node (ref "U1") (pin "15") (pinfunction "PA7_(PCINT7_/_ICP_/_OC0B_/_ADC7)_15") (pintype "bidirectional"))
    )
    (net (code "82") (name "VIO") (class "Default")
      (node (ref "J1") (pin "39") (pinfunction "39_39") (pintype "passive"))
      (node (ref "P1") (pin "1") (pinfunction "1_1") (pintype "passive"))
      (node (ref "P1") (pin "2") (pinfunction "2_2") (pintype "passive"))
      (node (ref "P2") (pin "1") (pinfunction "1_1") (pintype "passive"))
      (node (ref "P2") (pin "2") (pinfunction "2_2") (pintype "passive"))
      (node (ref "P3") (pin "1") (pinfunction "1_1") (pintype "passive"))
      (node (ref "P3") (pin "2") (pinfunction "2_2") (pintype "passive"))
      (node (ref "P4") (pin "1") (pinfunction "1_1") (pintype "passive"))
      (node (ref "P4") (pin "2") (pinfunction "2_2") (pintype "passive"))
    )
    (net (code "83") (name "unconnected-(MH1-Pad1)") (class "Default")
      (node (ref "MH1") (pin "1") (pinfunction "1_1") (pintype "passive+no_connect"))
    )
    (net (code "84") (name "unconnected-(MH2-Pad1)") (class "Default")
      (node (ref "MH2") (pin "1") (pinfunction "1_1") (pintype "passive+no_connect"))
    )
    (net (code "85") (name "unconnected-(MH3-Pad1)") (class "Default")
      (node (ref "MH3") (pin "1") (pinfunction "1_1") (pintype "passive+no_connect"))
    )
    (net (code "86") (name "unconnected-(MH4-Pad1)") (class "Default")
      (node (ref "MH4") (pin "1") (pinfunction "1_1") (pintype "passive+no_connect"))
    )
    (net (code "87") (name "unconnected-(MH5-Pad1)") (class "Default")
      (node (ref "MH5") (pin "1") (pinfunction "1_1") (pintype "passive+no_connect"))
    )
    (net (code "88") (name "unconnected-(MH6-Pad1)") (class "Default")
      (node (ref "MH6") (pin "1") (pinfunction "1_1") (pintype "passive+no_connect"))
    )
    (net (code "89") (name "unconnected-(U1-DNC-Pad6)") (class "Default")
      (node (ref "U1") (pin "6") (pinfunction "DNC_6") (pintype "passive+no_connect"))
    )
    (net (code "90") (name "unconnected-(U1-DNC-Pad7)") (class "Default")
      (node (ref "U1") (pin "7") (pinfunction "DNC_7") (pintype "passive+no_connect"))
    )
    (net (code "91") (name "unconnected-(U1-DNC-Pad10)") (class "Default")
      (node (ref "U1") (pin "10") (pinfunction "DNC_10") (pintype "passive+no_connect"))
    )
    (net (code "92") (name "unconnected-(U1-DNC-Pad17)") (class "Default")
      (node (ref "U1") (pin "17") (pinfunction "DNC_17") (pintype "passive+no_connect"))
    )
    (net (code "93") (name "unconnected-(U1-DNC-Pad18)") (class "Default")
      (node (ref "U1") (pin "18") (pinfunction "DNC_18") (pintype "passive+no_connect"))
    )
    (net (code "94") (name "unconnected-(U1-DNC-Pad19)") (class "Default")
      (node (ref "U1") (pin "19") (pinfunction "DNC_19") (pintype "passive+no_connect"))
    )
  )
)
